# DB4100_MCU.net
KiCad netlist of a schematic drawn in Altium Designer
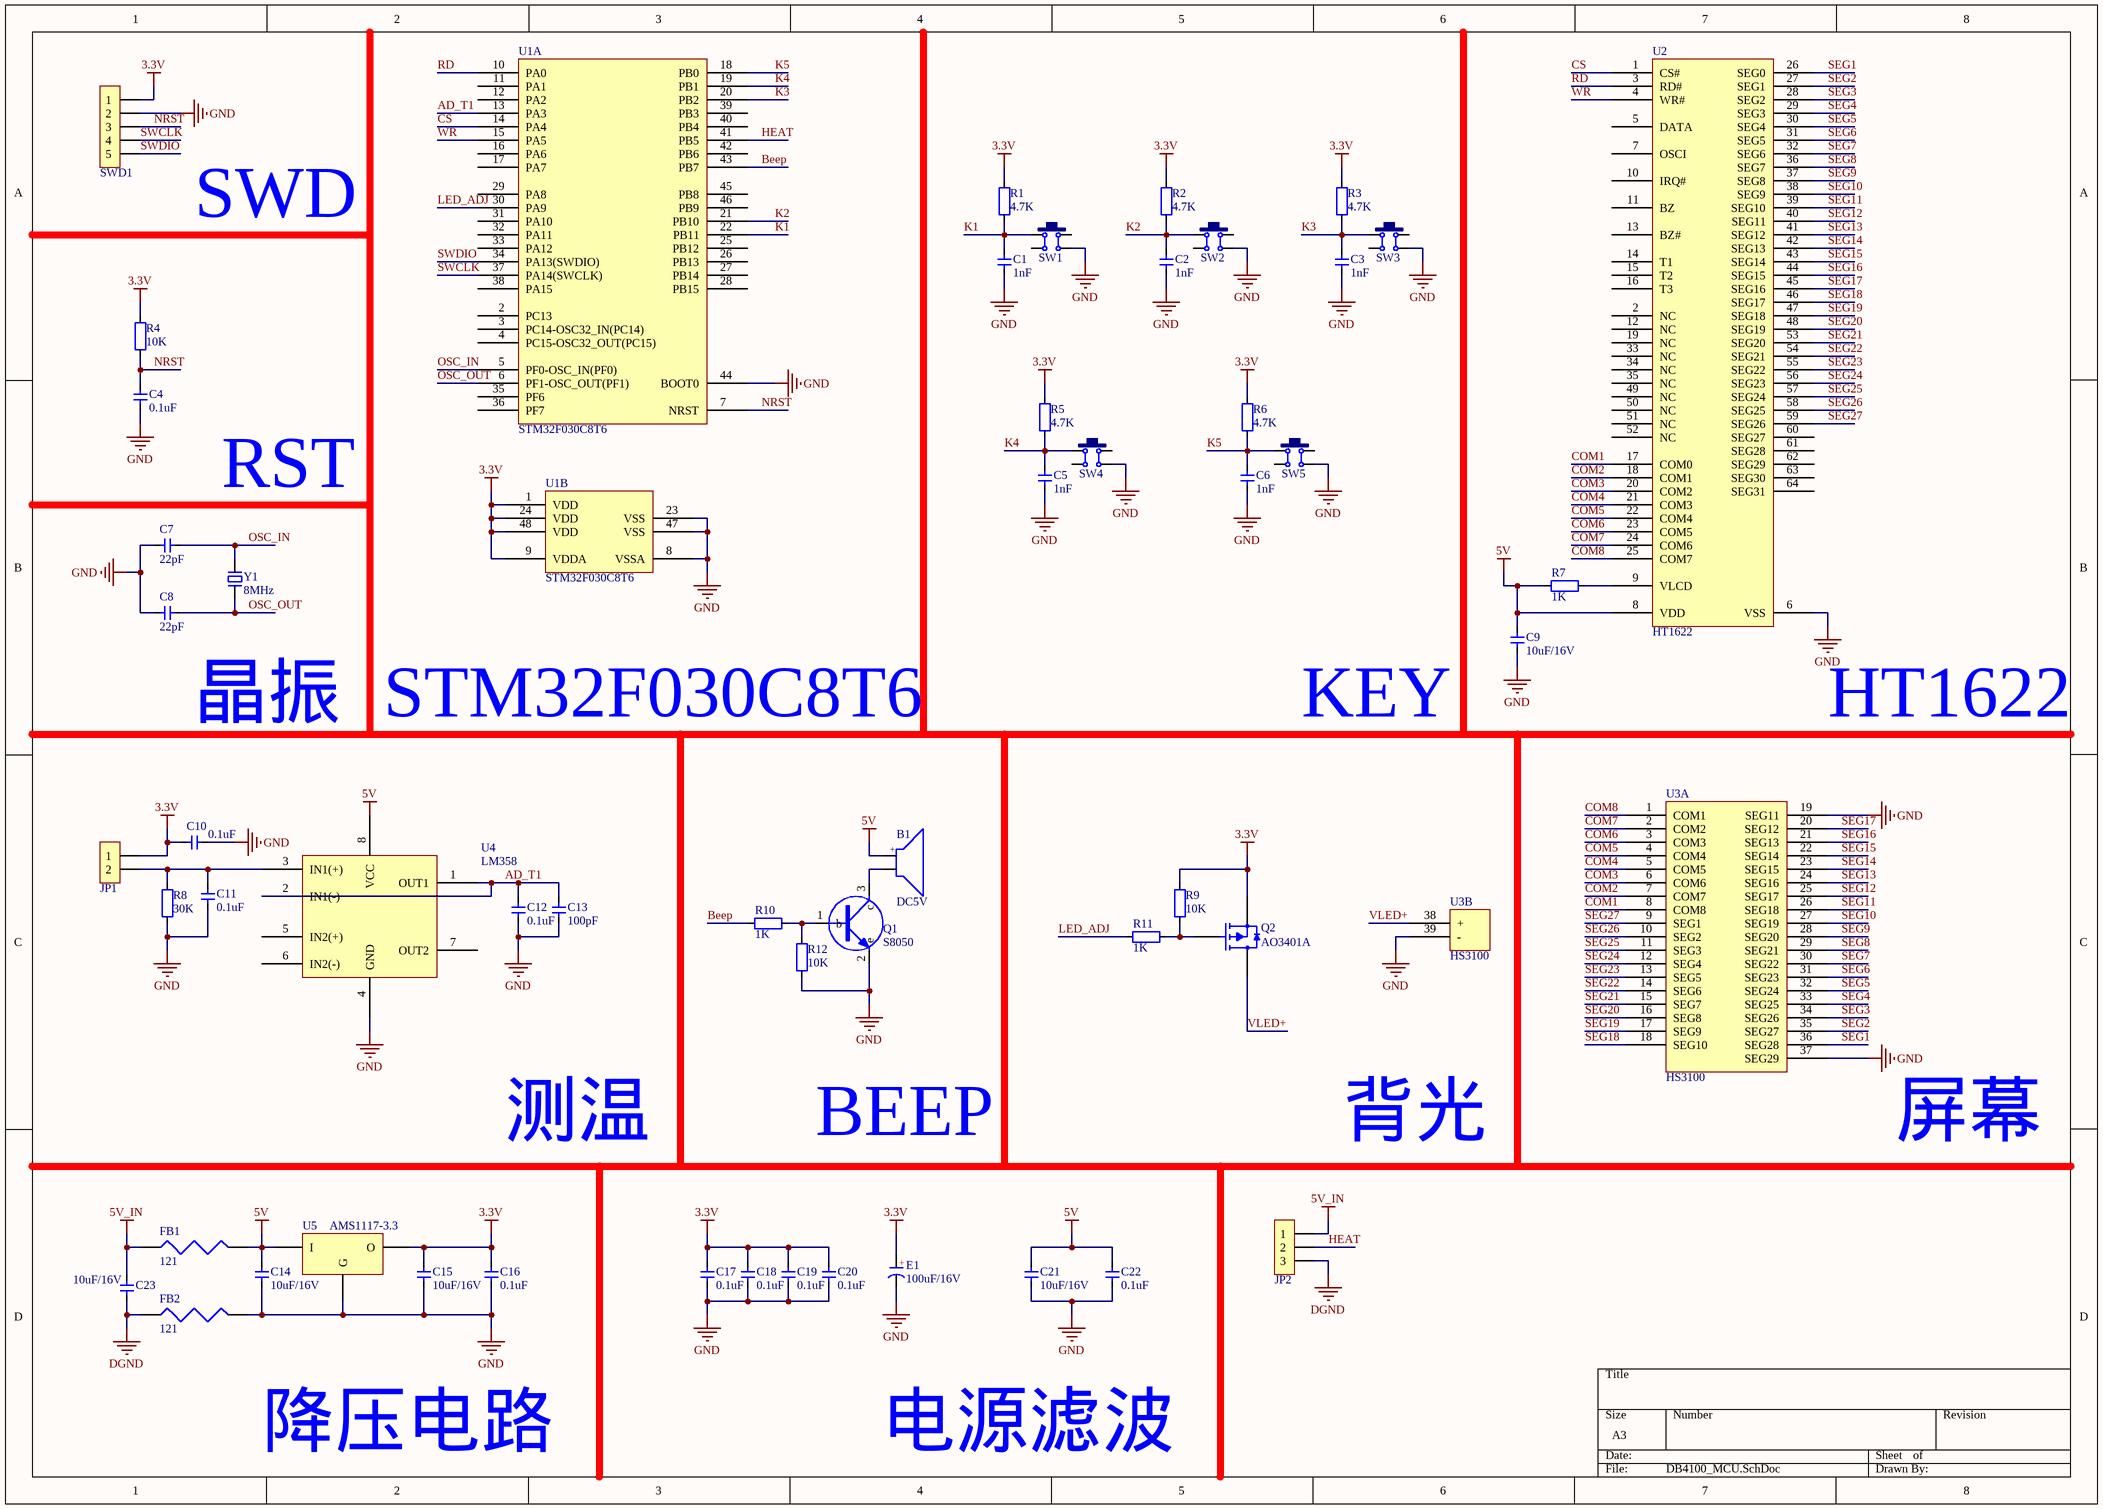
[diagram p0: DB4100_MCU.SchDoc]

(export (version "E")
  (design (tool "Eeschema 10.0.6"))
  (components
    (comp (ref "B1")
      (value "DC5V")
      (footprint "BEEP 7.6X12X7.5")
      (description "蜂鸣器")
      (fields (field (name "版权归属") "源创客"))
      (libsource (lib "模块器件") (part "BEEP"))
    )
    (comp (ref "C1")
      (value "1nF")
      (footprint "C 0603")
      (description "无极性贴片电容")
      (fields (field (name "版权归属") "源创客"))
      (libsource (lib "电容") (part "C"))
    )
    (comp (ref "C2")
      (value "1nF")
      (footprint "C 0603")
      (description "无极性贴片电容")
      (fields (field (name "版权归属") "源创客"))
      (libsource (lib "电容") (part "C"))
    )
    (comp (ref "C3")
      (value "1nF")
      (footprint "C 0603")
      (description "无极性贴片电容")
      (fields (field (name "版权归属") "源创客"))
      (libsource (lib "电容") (part "C"))
    )
    (comp (ref "C4")
      (value "0.1uF")
      (footprint "C 0603")
      (description "无极性贴片电容")
      (fields (field (name "版权归属") "源创客"))
      (libsource (lib "电容") (part "C"))
    )
    (comp (ref "C5")
      (value "1nF")
      (footprint "C 0603")
      (description "无极性贴片电容")
      (fields (field (name "版权归属") "源创客"))
      (libsource (lib "电容") (part "C"))
    )
    (comp (ref "C6")
      (value "1nF")
      (footprint "C 0603")
      (description "无极性贴片电容")
      (fields (field (name "版权归属") "源创客"))
      (libsource (lib "电容") (part "C"))
    )
    (comp (ref "C7")
      (value "22pF")
      (footprint "C 0603")
      (description "无极性贴片电容")
      (fields (field (name "版权归属") "源创客"))
      (libsource (lib "电容") (part "C"))
    )
    (comp (ref "C8")
      (value "22pF")
      (footprint "C 0603")
      (description "无极性贴片电容")
      (fields (field (name "版权归属") "源创客"))
      (libsource (lib "电容") (part "C"))
    )
    (comp (ref "C9")
      (value "10uF/16V")
      (footprint "C 0805")
      (description "无极性贴片电容")
      (fields (field (name "版权归属") "源创客"))
      (libsource (lib "电容") (part "C"))
    )
    (comp (ref "C10")
      (value "0.1uF")
      (footprint "C 0603")
      (description "无极性贴片电容")
      (fields (field (name "版权归属") "源创客"))
      (libsource (lib "电容") (part "C"))
    )
    (comp (ref "C11")
      (value "0.1uF")
      (footprint "C 0603")
      (description "无极性贴片电容")
      (fields (field (name "版权归属") "源创客"))
      (libsource (lib "电容") (part "C"))
    )
    (comp (ref "C12")
      (value "0.1uF")
      (footprint "C 0603")
      (description "无极性贴片电容")
      (fields (field (name "版权归属") "源创客"))
      (libsource (lib "电容") (part "C"))
    )
    (comp (ref "C13")
      (value "100pF")
      (footprint "C 0603")
      (description "无极性贴片电容")
      (fields (field (name "版权归属") "源创客"))
      (libsource (lib "电容") (part "C"))
    )
    (comp (ref "C14")
      (value "10uF/16V")
      (footprint "C 0805")
      (description "无极性贴片电容")
      (fields (field (name "版权归属") "源创客"))
      (libsource (lib "电容") (part "C"))
    )
    (comp (ref "C15")
      (value "10uF/16V")
      (footprint "C 0805")
      (description "无极性贴片电容")
      (fields (field (name "版权归属") "源创客"))
      (libsource (lib "电容") (part "C"))
    )
    (comp (ref "C16")
      (value "0.1uF")
      (footprint "C 0603")
      (description "无极性贴片电容")
      (fields (field (name "版权归属") "源创客"))
      (libsource (lib "电容") (part "C"))
    )
    (comp (ref "C17")
      (value "0.1uF")
      (footprint "C 0603")
      (description "无极性贴片电容")
      (fields (field (name "版权归属") "源创客"))
      (libsource (lib "电容") (part "C"))
    )
    (comp (ref "C18")
      (value "0.1uF")
      (footprint "C 0603")
      (description "无极性贴片电容")
      (fields (field (name "版权归属") "源创客"))
      (libsource (lib "电容") (part "C"))
    )
    (comp (ref "C19")
      (value "0.1uF")
      (footprint "C 0603")
      (description "无极性贴片电容")
      (fields (field (name "版权归属") "源创客"))
      (libsource (lib "电容") (part "C"))
    )
    (comp (ref "C20")
      (value "0.1uF")
      (footprint "C 0603")
      (description "无极性贴片电容")
      (fields (field (name "版权归属") "源创客"))
      (libsource (lib "电容") (part "C"))
    )
    (comp (ref "C21")
      (value "10uF/16V")
      (footprint "C 0805")
      (description "无极性贴片电容")
      (fields (field (name "版权归属") "源创客"))
      (libsource (lib "电容") (part "C"))
    )
    (comp (ref "C22")
      (value "0.1uF")
      (footprint "C 0603")
      (description "无极性贴片电容")
      (fields (field (name "版权归属") "源创客"))
      (libsource (lib "电容") (part "C"))
    )
    (comp (ref "C23")
      (value "10uF/16V")
      (footprint "C 0805")
      (description "无极性贴片电容")
      (fields (field (name "版权归属") "源创客"))
      (libsource (lib "电容") (part "C"))
    )
    (comp (ref "E1")
      (value "100uF/16V")
      (footprint "CM D(6.3*5.4)")
      (description "直插电解电容")
      (fields (field (name "版权归属") "源创客"))
      (libsource (lib "电容") (part "C-CAP"))
    )
    (comp (ref "FB1")
      (value "121")
      (footprint "L 0805")
      (description "磁珠")
      (libsource (lib "电感") (part "FB"))
    )
    (comp (ref "FB2")
      (value "121")
      (footprint "L 0805")
      (description "磁珠")
      (libsource (lib "电感") (part "FB"))
    )
    (comp (ref "JP1")
      (value "HDR-1X2")
      (footprint "XH2.54-2P")
      (description "2P接插件")
      (fields (field (name "版权归属") "源创客"))
      (libsource (lib "排针-排母") (part "Header 2"))
    )
    (comp (ref "JP2")
      (value "HDR-1X3")
      (footprint "XH2.54-3P")
      (description "3P接插件")
      (fields (field (name "版权归属") "源创客"))
      (libsource (lib "排针-排母") (part "Header 3"))
    )
    (comp (ref "Q1") (value "S8050") (footprint "SOT23-3L") (libsource (lib "三极管") (part "NPN")))
    (comp (ref "Q2")
      (value "AO3401A")
      (footprint "SOT23-3")
      (description "P-MOS")
      (libsource (lib "三极管") (part "AO3401A"))
    )
    (comp (ref "R1")
      (value "4.7K")
      (footprint "R 0603")
      (description "贴片电阻")
      (fields (field (name "版权归属") "源创客"))
      (libsource (lib "") (part "R_1"))
    )
    (comp (ref "R2")
      (value "4.7K")
      (footprint "R 0603")
      (description "贴片电阻")
      (fields (field (name "版权归属") "源创客"))
      (libsource (lib "") (part "R_1"))
    )
    (comp (ref "R3")
      (value "4.7K")
      (footprint "R 0603")
      (description "贴片电阻")
      (fields (field (name "版权归属") "源创客"))
      (libsource (lib "") (part "R_1"))
    )
    (comp (ref "R4")
      (value "10K")
      (footprint "R 0603")
      (description "贴片电阻")
      (fields (field (name "版权归属") "源创客"))
      (libsource (lib "") (part "R_1"))
    )
    (comp (ref "R5")
      (value "4.7K")
      (footprint "R 0603")
      (description "贴片电阻")
      (fields (field (name "版权归属") "源创客"))
      (libsource (lib "") (part "R_1"))
    )
    (comp (ref "R6")
      (value "4.7K")
      (footprint "R 0603")
      (description "贴片电阻")
      (fields (field (name "版权归属") "源创客"))
      (libsource (lib "") (part "R_1"))
    )
    (comp (ref "R7")
      (value "1K")
      (footprint "R 0603")
      (description "贴片电阻")
      (fields (field (name "版权归属") "源创客"))
      (libsource (lib "电阻") (part "R"))
    )
    (comp (ref "R8")
      (value "30K")
      (footprint "R 0603")
      (description "贴片电阻")
      (fields (field (name "版权归属") "源创客"))
      (libsource (lib "") (part "R_1"))
    )
    (comp (ref "R9")
      (value "10K")
      (footprint "R 0603")
      (description "贴片电阻")
      (fields (field (name "版权归属") "源创客"))
      (libsource (lib "") (part "R_1"))
    )
    (comp (ref "R10")
      (value "1K")
      (footprint "R 0603")
      (description "贴片电阻")
      (fields (field (name "版权归属") "源创客"))
      (libsource (lib "电阻") (part "R"))
    )
    (comp (ref "R11")
      (value "1K")
      (footprint "R 0603")
      (description "贴片电阻")
      (fields (field (name "版权归属") "源创客"))
      (libsource (lib "电阻") (part "R"))
    )
    (comp (ref "R12")
      (value "10K")
      (footprint "R 0603")
      (description "贴片电阻")
      (fields (field (name "版权归属") "源创客"))
      (libsource (lib "") (part "R_1"))
    )
    (comp (ref "SW1")
      (value "6x6x5")
      (footprint "TSW SMD-6*6*7")
      (description "贴片6x6轻触开关")
      (fields (field (name "版权归属") "源创客"))
      (libsource (lib "按键") (part "TSW SMD-6x6"))
    )
    (comp (ref "SW2")
      (value "6x6x5")
      (footprint "TSW SMD-6*6*7")
      (description "贴片6x6轻触开关")
      (fields (field (name "版权归属") "源创客"))
      (libsource (lib "按键") (part "TSW SMD-6x6"))
    )
    (comp (ref "SW3")
      (value "6x6x5")
      (footprint "TSW SMD-6*6*7")
      (description "贴片6x6轻触开关")
      (fields (field (name "版权归属") "源创客"))
      (libsource (lib "按键") (part "TSW SMD-6x6"))
    )
    (comp (ref "SW4")
      (value "6x6x5")
      (footprint "TSW SMD-6*6*7")
      (description "贴片6x6轻触开关")
      (fields (field (name "版权归属") "源创客"))
      (libsource (lib "按键") (part "TSW SMD-6x6"))
    )
    (comp (ref "SW5")
      (value "6x6x5")
      (footprint "TSW SMD-6*6*7")
      (description "贴片6x6轻触开关")
      (fields (field (name "版权归属") "源创客"))
      (libsource (lib "按键") (part "TSW SMD-6x6"))
    )
    (comp (ref "SWD1")
      (value "HDR-1X5")
      (footprint "XH2.54-5P")
      (description "5P接插件")
      (fields (field (name "版权归属") "源创客"))
      (libsource (lib "排针-排母") (part "Header 5"))
    )
    (comp (ref "U1")
      (value "STM32F030C8T6")
      (footprint "STM32F030C8T6")
      (libsource (lib "STM32系列单片机") (part "STM32F030C8T6"))
    )
    (comp (ref "U2")
      (value "HT1622")
      (footprint "HT1622")
      (description "LCD驱动，64引脚")
      (libsource (lib "显示芯片") (part "HT1622"))
    )
    (comp (ref "U3")
      (value "HS3100")
      (footprint "HS3100")
      (description "HS3100的屏幕")
      (libsource (lib "显示屏幕") (part "HS3100"))
    )
    (comp (ref "U4")
      (value "LM358")
      (footprint "LM358")
      (description "LM358是由两个独立的高增益运算放大器组成")
      (libsource (lib "常用芯片") (part "LM358"))
    )
    (comp (ref "U5")
      (value "AMS1117-3.3")
      (footprint "AMS1117-3.3")
      (description "转3.3V电压")
      (libsource (lib "变压器") (part "AMS1117-3.3"))
    )
    (comp (ref "Y1")
      (value "8MHz")
      (footprint "XTAL-49S SMD")
      (description "2脚晶振")
      (fields (field (name "版权归属") "源创客"))
      (libsource (lib "晶振") (part "XTAL-2"))
    )
  )
  (nets
    (net (code "1") (name "/AD_T1") (class "Default")
      (node (ref "C12") (pin "2") (pinfunction "2_2") (pintype "passive"))
      (node (ref "C13") (pin "2") (pinfunction "2_2") (pintype "passive"))
      (node (ref "U1") (pin "13") (pinfunction "PA3_13") (pintype "passive"))
      (node (ref "U4") (pin "1") (pinfunction "OUT1_1") (pintype "passive"))
      (node (ref "U4") (pin "2") (pinfunction "IN1(-)_2") (pintype "passive"))
    )
    (net (code "2") (name "/Beep") (class "Default")
      (node (ref "R10") (pin "1") (pinfunction "1_1") (pintype "passive"))
      (node (ref "U1") (pin "43") (pinfunction "PB7_43") (pintype "passive"))
    )
    (net (code "3") (name "/COM1") (class "Default")
      (node (ref "U2") (pin "17") (pinfunction "COM0_17") (pintype "passive"))
      (node (ref "U3") (pin "8") (pinfunction "COM8_8") (pintype "passive"))
    )
    (net (code "4") (name "/COM2") (class "Default")
      (node (ref "U2") (pin "18") (pinfunction "COM1_18") (pintype "passive"))
      (node (ref "U3") (pin "7") (pinfunction "COM7_7") (pintype "passive"))
    )
    (net (code "5") (name "/COM3") (class "Default")
      (node (ref "U2") (pin "20") (pinfunction "COM2_20") (pintype "passive"))
      (node (ref "U3") (pin "6") (pinfunction "COM6_6") (pintype "passive"))
    )
    (net (code "6") (name "/COM4") (class "Default")
      (node (ref "U2") (pin "21") (pinfunction "COM3_21") (pintype "passive"))
      (node (ref "U3") (pin "5") (pinfunction "COM5_5") (pintype "passive"))
    )
    (net (code "7") (name "/COM5") (class "Default")
      (node (ref "U2") (pin "22") (pinfunction "COM4_22") (pintype "passive"))
      (node (ref "U3") (pin "4") (pinfunction "COM4_4") (pintype "passive"))
    )
    (net (code "8") (name "/COM6") (class "Default")
      (node (ref "U2") (pin "23") (pinfunction "COM5_23") (pintype "passive"))
      (node (ref "U3") (pin "3") (pinfunction "COM3_3") (pintype "passive"))
    )
    (net (code "9") (name "/COM7") (class "Default")
      (node (ref "U2") (pin "24") (pinfunction "COM6_24") (pintype "passive"))
      (node (ref "U3") (pin "2") (pinfunction "COM2_2") (pintype "passive"))
    )
    (net (code "10") (name "/COM8") (class "Default")
      (node (ref "U2") (pin "25") (pinfunction "COM7_25") (pintype "passive"))
      (node (ref "U3") (pin "1") (pinfunction "COM1_1") (pintype "passive"))
    )
    (net (code "11") (name "/CS") (class "Default")
      (node (ref "U1") (pin "14") (pinfunction "PA4_14") (pintype "passive"))
      (node (ref "U2") (pin "1") (pinfunction "CS#_1") (pintype "passive"))
    )
    (net (code "12") (name "/HEAT") (class "Default")
      (node (ref "JP2") (pin "2") (pinfunction "2_2") (pintype "passive"))
      (node (ref "U1") (pin "41") (pinfunction "PB5_41") (pintype "passive"))
    )
    (net (code "13") (name "/K1") (class "Default")
      (node (ref "C1") (pin "2") (pinfunction "2_2") (pintype "passive"))
      (node (ref "R1") (pin "1") (pinfunction "1_1") (pintype "passive"))
      (node (ref "SW1") (pin "1") (pinfunction "1_1") (pintype "passive"))
      (node (ref "U1") (pin "22") (pinfunction "PB11_22") (pintype "passive"))
    )
    (net (code "14") (name "/K2") (class "Default")
      (node (ref "C2") (pin "2") (pinfunction "2_2") (pintype "passive"))
      (node (ref "R2") (pin "1") (pinfunction "1_1") (pintype "passive"))
      (node (ref "SW2") (pin "1") (pinfunction "1_1") (pintype "passive"))
      (node (ref "U1") (pin "21") (pinfunction "PB10_21") (pintype "passive"))
    )
    (net (code "15") (name "/K3") (class "Default")
      (node (ref "C3") (pin "2") (pinfunction "2_2") (pintype "passive"))
      (node (ref "R3") (pin "1") (pinfunction "1_1") (pintype "passive"))
      (node (ref "SW3") (pin "1") (pinfunction "1_1") (pintype "passive"))
      (node (ref "U1") (pin "20") (pinfunction "PB2_20") (pintype "passive"))
    )
    (net (code "16") (name "/K4") (class "Default")
      (node (ref "C5") (pin "2") (pinfunction "2_2") (pintype "passive"))
      (node (ref "R5") (pin "1") (pinfunction "1_1") (pintype "passive"))
      (node (ref "SW4") (pin "1") (pinfunction "1_1") (pintype "passive"))
      (node (ref "U1") (pin "19") (pinfunction "PB1_19") (pintype "passive"))
    )
    (net (code "17") (name "/K5") (class "Default")
      (node (ref "C6") (pin "2") (pinfunction "2_2") (pintype "passive"))
      (node (ref "R6") (pin "1") (pinfunction "1_1") (pintype "passive"))
      (node (ref "SW5") (pin "1") (pinfunction "1_1") (pintype "passive"))
      (node (ref "U1") (pin "18") (pinfunction "PB0_18") (pintype "passive"))
    )
    (net (code "18") (name "/LED_ADJ") (class "Default")
      (node (ref "R11") (pin "1") (pinfunction "1_1") (pintype "passive"))
      (node (ref "U1") (pin "30") (pinfunction "PA9_30") (pintype "passive"))
    )
    (net (code "19") (name "/NRST") (class "Default")
      (node (ref "C4") (pin "2") (pinfunction "2_2") (pintype "passive"))
      (node (ref "R4") (pin "1") (pinfunction "1_1") (pintype "passive"))
      (node (ref "SWD1") (pin "3") (pinfunction "3_3") (pintype "passive"))
      (node (ref "U1") (pin "7") (pinfunction "NRST_7") (pintype "passive"))
    )
    (net (code "20") (name "/OSC_IN") (class "Default")
      (node (ref "C7") (pin "2") (pinfunction "2_2") (pintype "passive"))
      (node (ref "U1") (pin "5") (pinfunction "PF0-OSC_IN(PF0)_5") (pintype "passive"))
      (node (ref "Y1") (pin "2") (pinfunction "2_2") (pintype "passive"))
    )
    (net (code "21") (name "/OSC_OUT") (class "Default")
      (node (ref "C8") (pin "2") (pinfunction "2_2") (pintype "passive"))
      (node (ref "U1") (pin "6") (pinfunction "PF1-OSC_OUT(PF1)_6") (pintype "passive"))
      (node (ref "Y1") (pin "1") (pinfunction "1_1") (pintype "passive"))
    )
    (net (code "22") (name "/RD") (class "Default")
      (node (ref "U1") (pin "10") (pinfunction "PA0_10") (pintype "passive"))
      (node (ref "U2") (pin "3") (pinfunction "RD#_3") (pintype "passive"))
    )
    (net (code "23") (name "/SEG1") (class "Default")
      (node (ref "U2") (pin "26") (pinfunction "SEG0_26") (pintype "passive"))
      (node (ref "U3") (pin "36") (pinfunction "SEG28_36") (pintype "passive"))
    )
    (net (code "24") (name "/SEG2") (class "Default")
      (node (ref "U2") (pin "27") (pinfunction "SEG1_27") (pintype "passive"))
      (node (ref "U3") (pin "35") (pinfunction "SEG27_35") (pintype "passive"))
    )
    (net (code "25") (name "/SEG3") (class "Default")
      (node (ref "U2") (pin "28") (pinfunction "SEG2_28") (pintype "passive"))
      (node (ref "U3") (pin "34") (pinfunction "SEG26_34") (pintype "passive"))
    )
    (net (code "26") (name "/SEG4") (class "Default")
      (node (ref "U2") (pin "29") (pinfunction "SEG3_29") (pintype "passive"))
      (node (ref "U3") (pin "33") (pinfunction "SEG25_33") (pintype "passive"))
    )
    (net (code "27") (name "/SEG5") (class "Default")
      (node (ref "U2") (pin "30") (pinfunction "SEG4_30") (pintype "passive"))
      (node (ref "U3") (pin "32") (pinfunction "SEG24_32") (pintype "passive"))
    )
    (net (code "28") (name "/SEG6") (class "Default")
      (node (ref "U2") (pin "31") (pinfunction "SEG5_31") (pintype "passive"))
      (node (ref "U3") (pin "31") (pinfunction "SEG23_31") (pintype "passive"))
    )
    (net (code "29") (name "/SEG7") (class "Default")
      (node (ref "U2") (pin "32") (pinfunction "SEG6_32") (pintype "passive"))
      (node (ref "U3") (pin "30") (pinfunction "SEG22_30") (pintype "passive"))
    )
    (net (code "30") (name "/SEG8") (class "Default")
      (node (ref "U2") (pin "36") (pinfunction "SEG7_36") (pintype "passive"))
      (node (ref "U3") (pin "29") (pinfunction "SEG21_29") (pintype "passive"))
    )
    (net (code "31") (name "/SEG9") (class "Default")
      (node (ref "U2") (pin "37") (pinfunction "SEG8_37") (pintype "passive"))
      (node (ref "U3") (pin "28") (pinfunction "SEG20_28") (pintype "passive"))
    )
    (net (code "32") (name "/SEG10") (class "Default")
      (node (ref "U2") (pin "38") (pinfunction "SEG9_38") (pintype "passive"))
      (node (ref "U3") (pin "27") (pinfunction "SEG19_27") (pintype "passive"))
    )
    (net (code "33") (name "/SEG11") (class "Default")
      (node (ref "U2") (pin "39") (pinfunction "SEG10_39") (pintype "passive"))
      (node (ref "U3") (pin "26") (pinfunction "SEG18_26") (pintype "passive"))
    )
    (net (code "34") (name "/SEG12") (class "Default")
      (node (ref "U2") (pin "40") (pinfunction "SEG11_40") (pintype "passive"))
      (node (ref "U3") (pin "25") (pinfunction "SEG17_25") (pintype "passive"))
    )
    (net (code "35") (name "/SEG13") (class "Default")
      (node (ref "U2") (pin "41") (pinfunction "SEG12_41") (pintype "passive"))
      (node (ref "U3") (pin "24") (pinfunction "SEG16_24") (pintype "passive"))
    )
    (net (code "36") (name "/SEG14") (class "Default")
      (node (ref "U2") (pin "42") (pinfunction "SEG13_42") (pintype "passive"))
      (node (ref "U3") (pin "23") (pinfunction "SEG15_23") (pintype "passive"))
    )
    (net (code "37") (name "/SEG15") (class "Default")
      (node (ref "U2") (pin "43") (pinfunction "SEG14_43") (pintype "passive"))
      (node (ref "U3") (pin "22") (pinfunction "SEG14_22") (pintype "passive"))
    )
    (net (code "38") (name "/SEG16") (class "Default")
      (node (ref "U2") (pin "44") (pinfunction "SEG15_44") (pintype "passive"))
      (node (ref "U3") (pin "21") (pinfunction "SEG13_21") (pintype "passive"))
    )
    (net (code "39") (name "/SEG17") (class "Default")
      (node (ref "U2") (pin "45") (pinfunction "SEG16_45") (pintype "passive"))
      (node (ref "U3") (pin "20") (pinfunction "SEG12_20") (pintype "passive"))
    )
    (net (code "40") (name "/SEG18") (class "Default")
      (node (ref "U2") (pin "46") (pinfunction "SEG17_46") (pintype "passive"))
      (node (ref "U3") (pin "18") (pinfunction "SEG10_18") (pintype "passive"))
    )
    (net (code "41") (name "/SEG19") (class "Default")
      (node (ref "U2") (pin "47") (pinfunction "SEG18_47") (pintype "passive"))
      (node (ref "U3") (pin "17") (pinfunction "SEG9_17") (pintype "passive"))
    )
    (net (code "42") (name "/SEG20") (class "Default")
      (node (ref "U2") (pin "48") (pinfunction "SEG19_48") (pintype "passive"))
      (node (ref "U3") (pin "16") (pinfunction "SEG8_16") (pintype "passive"))
    )
    (net (code "43") (name "/SEG21") (class "Default")
      (node (ref "U2") (pin "53") (pinfunction "SEG20_53") (pintype "passive"))
      (node (ref "U3") (pin "15") (pinfunction "SEG7_15") (pintype "passive"))
    )
    (net (code "44") (name "/SEG22") (class "Default")
      (node (ref "U2") (pin "54") (pinfunction "SEG21_54") (pintype "passive"))
      (node (ref "U3") (pin "14") (pinfunction "SEG6_14") (pintype "passive"))
    )
    (net (code "45") (name "/SEG23") (class "Default")
      (node (ref "U2") (pin "55") (pinfunction "SEG22_55") (pintype "passive"))
      (node (ref "U3") (pin "13") (pinfunction "SEG5_13") (pintype "passive"))
    )
    (net (code "46") (name "/SEG24") (class "Default")
      (node (ref "U2") (pin "56") (pinfunction "SEG23_56") (pintype "passive"))
      (node (ref "U3") (pin "12") (pinfunction "SEG4_12") (pintype "passive"))
    )
    (net (code "47") (name "/SEG25") (class "Default")
      (node (ref "U2") (pin "57") (pinfunction "SEG24_57") (pintype "passive"))
      (node (ref "U3") (pin "11") (pinfunction "SEG3_11") (pintype "passive"))
    )
    (net (code "48") (name "/SEG26") (class "Default")
      (node (ref "U2") (pin "58") (pinfunction "SEG25_58") (pintype "passive"))
      (node (ref "U3") (pin "10") (pinfunction "SEG2_10") (pintype "passive"))
    )
    (net (code "49") (name "/SEG27") (class "Default")
      (node (ref "U2") (pin "59") (pinfunction "SEG26_59") (pintype "passive"))
      (node (ref "U3") (pin "9") (pinfunction "SEG1_9") (pintype "passive"))
    )
    (net (code "50") (name "/SWCLK") (class "Default")
      (node (ref "SWD1") (pin "4") (pinfunction "4_4") (pintype "passive"))
      (node (ref "U1") (pin "37") (pinfunction "PA14(SWCLK)_37") (pintype "passive"))
    )
    (net (code "51") (name "/SWDIO") (class "Default")
      (node (ref "SWD1") (pin "5") (pinfunction "5_5") (pintype "passive"))
      (node (ref "U1") (pin "34") (pinfunction "PA13(SWDIO)_34") (pintype "passive"))
    )
    (net (code "52") (name "/VLED+") (class "Default")
      (node (ref "Q2") (pin "3") (pinfunction "D_3") (pintype "passive"))
      (node (ref "U3") (pin "38") (pinfunction "+_38") (pintype "passive"))
    )
    (net (code "53") (name "/WR") (class "Default")
      (node (ref "U1") (pin "15") (pinfunction "PA5_15") (pintype "passive"))
      (node (ref "U2") (pin "4") (pinfunction "WR#_4") (pintype "passive"))
    )
    (net (code "54") (name "3.3V") (class "Default")
      (node (ref "C10") (pin "1") (pinfunction "1_1") (pintype "passive"))
      (node (ref "C15") (pin "2") (pinfunction "2_2") (pintype "passive"))
      (node (ref "C16") (pin "2") (pinfunction "2_2") (pintype "passive"))
      (node (ref "C17") (pin "2") (pinfunction "2_2") (pintype "passive"))
      (node (ref "C18") (pin "2") (pinfunction "2_2") (pintype "passive"))
      (node (ref "C19") (pin "2") (pinfunction "2_2") (pintype "passive"))
      (node (ref "C20") (pin "2") (pinfunction "2_2") (pintype "passive"))
      (node (ref "E1") (pin "1") (pinfunction "A_1") (pintype "passive"))
      (node (ref "JP1") (pin "1") (pinfunction "1_1") (pintype "passive"))
      (node (ref "Q2") (pin "2") (pinfunction "S_2") (pintype "passive"))
      (node (ref "R1") (pin "2") (pinfunction "2_2") (pintype "passive"))
      (node (ref "R2") (pin "2") (pinfunction "2_2") (pintype "passive"))
      (node (ref "R3") (pin "2") (pinfunction "2_2") (pintype "passive"))
      (node (ref "R4") (pin "2") (pinfunction "2_2") (pintype "passive"))
      (node (ref "R5") (pin "2") (pinfunction "2_2") (pintype "passive"))
      (node (ref "R6") (pin "2") (pinfunction "2_2") (pintype "passive"))
      (node (ref "R9") (pin "2") (pinfunction "2_2") (pintype "passive"))
      (node (ref "SWD1") (pin "1") (pinfunction "1_1") (pintype "passive"))
      (node (ref "U1") (pin "1") (pinfunction "VDD_1") (pintype "passive"))
      (node (ref "U1") (pin "24") (pinfunction "VDD_24") (pintype "passive"))
      (node (ref "U1") (pin "48") (pinfunction "VDD_48") (pintype "passive"))
      (node (ref "U1") (pin "9") (pinfunction "VDDA_9") (pintype "passive"))
      (node (ref "U5") (pin "2") (pinfunction "O_2") (pintype "passive"))
    )
    (net (code "55") (name "5V") (class "Default")
      (node (ref "B1") (pin "1") (pinfunction "1_1") (pintype "passive"))
      (node (ref "C14") (pin "2") (pinfunction "2_2") (pintype "passive"))
      (node (ref "C21") (pin "2") (pinfunction "2_2") (pintype "passive"))
      (node (ref "C22") (pin "2") (pinfunction "2_2") (pintype "passive"))
      (node (ref "C9") (pin "2") (pinfunction "2_2") (pintype "passive"))
      (node (ref "FB1") (pin "2") (pinfunction "2_2") (pintype "passive"))
      (node (ref "R7") (pin "1") (pinfunction "1_1") (pintype "passive"))
      (node (ref "U2") (pin "8") (pinfunction "VDD_8") (pintype "passive"))
      (node (ref "U4") (pin "8") (pinfunction "VCC_8") (pintype "passive"))
      (node (ref "U5") (pin "3") (pinfunction "I_3") (pintype "passive"))
    )
    (net (code "56") (name "5V_IN") (class "Default")
      (node (ref "C23") (pin "2") (pinfunction "2_2") (pintype "passive"))
      (node (ref "FB1") (pin "1") (pinfunction "1_1") (pintype "passive"))
      (node (ref "JP2") (pin "1") (pinfunction "1_1") (pintype "passive"))
    )
    (net (code "57") (name "DGND") (class "Default")
      (node (ref "C23") (pin "1") (pinfunction "1_1") (pintype "passive"))
      (node (ref "FB2") (pin "1") (pinfunction "1_1") (pintype "passive"))
      (node (ref "JP2") (pin "3") (pinfunction "3_3") (pintype "passive"))
    )
    (net (code "58") (name "GND") (class "Default")
      (node (ref "C1") (pin "1") (pinfunction "1_1") (pintype "passive"))
      (node (ref "C10") (pin "2") (pinfunction "2_2") (pintype "passive"))
      (node (ref "C11") (pin "1") (pinfunction "1_1") (pintype "passive"))
      (node (ref "C12") (pin "1") (pinfunction "1_1") (pintype "passive"))
      (node (ref "C13") (pin "1") (pinfunction "1_1") (pintype "passive"))
      (node (ref "C14") (pin "1") (pinfunction "1_1") (pintype "passive"))
      (node (ref "C15") (pin "1") (pinfunction "1_1") (pintype "passive"))
      (node (ref "C16") (pin "1") (pinfunction "1_1") (pintype "passive"))
      (node (ref "C17") (pin "1") (pinfunction "1_1") (pintype "passive"))
      (node (ref "C18") (pin "1") (pinfunction "1_1") (pintype "passive"))
      (node (ref "C19") (pin "1") (pinfunction "1_1") (pintype "passive"))
      (node (ref "C2") (pin "1") (pinfunction "1_1") (pintype "passive"))
      (node (ref "C20") (pin "1") (pinfunction "1_1") (pintype "passive"))
      (node (ref "C21") (pin "1") (pinfunction "1_1") (pintype "passive"))
      (node (ref "C22") (pin "1") (pinfunction "1_1") (pintype "passive"))
      (node (ref "C3") (pin "1") (pinfunction "1_1") (pintype "passive"))
      (node (ref "C4") (pin "1") (pinfunction "1_1") (pintype "passive"))
      (node (ref "C5") (pin "1") (pinfunction "1_1") (pintype "passive"))
      (node (ref "C6") (pin "1") (pinfunction "1_1") (pintype "passive"))
      (node (ref "C7") (pin "1") (pinfunction "1_1") (pintype "passive"))
      (node (ref "C8") (pin "1") (pinfunction "1_1") (pintype "passive"))
      (node (ref "C9") (pin "1") (pinfunction "1_1") (pintype "passive"))
      (node (ref "E1") (pin "2") (pinfunction "K_2") (pintype "passive"))
      (node (ref "FB2") (pin "2") (pinfunction "2_2") (pintype "passive"))
      (node (ref "Q1") (pin "2") (pinfunction "e_2") (pintype "passive"))
      (node (ref "R12") (pin "1") (pinfunction "1_1") (pintype "passive"))
      (node (ref "R8") (pin "1") (pinfunction "1_1") (pintype "passive"))
      (node (ref "SW1") (pin "3") (pinfunction "3_3") (pintype "passive"))
      (node (ref "SW2") (pin "3") (pinfunction "3_3") (pintype "passive"))
      (node (ref "SW3") (pin "3") (pinfunction "3_3") (pintype "passive"))
      (node (ref "SW4") (pin "3") (pinfunction "3_3") (pintype "passive"))
      (node (ref "SW5") (pin "3") (pinfunction "3_3") (pintype "passive"))
      (node (ref "SWD1") (pin "2") (pinfunction "2_2") (pintype "passive"))
      (node (ref "U1") (pin "23") (pinfunction "VSS_23") (pintype "passive"))
      (node (ref "U1") (pin "44") (pinfunction "BOOT0_44") (pintype "passive"))
      (node (ref "U1") (pin "47") (pinfunction "VSS_47") (pintype "passive"))
      (node (ref "U1") (pin "8") (pinfunction "VSSA_8") (pintype "passive"))
      (node (ref "U2") (pin "6") (pinfunction "VSS_6") (pintype "passive"))
      (node (ref "U3") (pin "19") (pinfunction "SEG11_19") (pintype "passive"))
      (node (ref "U3") (pin "37") (pinfunction "SEG29_37") (pintype "passive"))
      (node (ref "U3") (pin "39") (pinfunction "-_39") (pintype "passive"))
      (node (ref "U4") (pin "4") (pinfunction "GND_4") (pintype "passive"))
      (node (ref "U5") (pin "1") (pinfunction "G_1") (pintype "passive"))
    )
    (net (code "59") (name "Net-(Q1-b)") (class "Default")
      (node (ref "Q1") (pin "1") (pinfunction "b_1") (pintype "passive"))
      (node (ref "R10") (pin "2") (pinfunction "2_2") (pintype "passive"))
      (node (ref "R12") (pin "2") (pinfunction "2_2") (pintype "passive"))
    )
    (net (code "60") (name "Net-(Q1-c)") (class "Default")
      (node (ref "B1") (pin "2") (pinfunction "2_2") (pintype "passive"))
      (node (ref "Q1") (pin "3") (pinfunction "c_3") (pintype "passive"))
    )
    (net (code "61") (name "Net-(Q2-G)") (class "Default")
      (node (ref "Q2") (pin "1") (pinfunction "G_1") (pintype "passive"))
      (node (ref "R11") (pin "2") (pinfunction "2_2") (pintype "passive"))
      (node (ref "R9") (pin "1") (pinfunction "1_1") (pintype "passive"))
    )
    (net (code "62") (name "Net-(U2-VLCD)") (class "Default")
      (node (ref "R7") (pin "2") (pinfunction "2_2") (pintype "passive"))
      (node (ref "U2") (pin "9") (pinfunction "VLCD_9") (pintype "passive"))
    )
    (net (code "63") (name "Net-(U4-IN1(+))") (class "Default")
      (node (ref "C11") (pin "2") (pinfunction "2_2") (pintype "passive"))
      (node (ref "JP1") (pin "2") (pinfunction "2_2") (pintype "passive"))
      (node (ref "R8") (pin "2") (pinfunction "2_2") (pintype "passive"))
      (node (ref "U4") (pin "3") (pinfunction "IN1(+)_3") (pintype "passive"))
    )
    (net (code "64") (name "unconnected-(SW1-Pad2)") (class "Default")
      (node (ref "SW1") (pin "2") (pinfunction "2_2") (pintype "passive"))
    )
    (net (code "65") (name "unconnected-(SW1-Pad4)") (class "Default")
      (node (ref "SW1") (pin "4") (pinfunction "4_4") (pintype "passive"))
    )
    (net (code "66") (name "unconnected-(SW2-Pad2)") (class "Default")
      (node (ref "SW2") (pin "2") (pinfunction "2_2") (pintype "passive"))
    )
    (net (code "67") (name "unconnected-(SW2-Pad4)") (class "Default")
      (node (ref "SW2") (pin "4") (pinfunction "4_4") (pintype "passive"))
    )
    (net (code "68") (name "unconnected-(SW3-Pad2)") (class "Default")
      (node (ref "SW3") (pin "2") (pinfunction "2_2") (pintype "passive"))
    )
    (net (code "69") (name "unconnected-(SW3-Pad4)") (class "Default")
      (node (ref "SW3") (pin "4") (pinfunction "4_4") (pintype "passive"))
    )
    (net (code "70") (name "unconnected-(SW4-Pad2)") (class "Default")
      (node (ref "SW4") (pin "2") (pinfunction "2_2") (pintype "passive"))
    )
    (net (code "71") (name "unconnected-(SW4-Pad4)") (class "Default")
      (node (ref "SW4") (pin "4") (pinfunction "4_4") (pintype "passive"))
    )
    (net (code "72") (name "unconnected-(SW5-Pad2)") (class "Default")
      (node (ref "SW5") (pin "2") (pinfunction "2_2") (pintype "passive"))
    )
    (net (code "73") (name "unconnected-(SW5-Pad4)") (class "Default")
      (node (ref "SW5") (pin "4") (pinfunction "4_4") (pintype "passive"))
    )
    (net (code "74") (name "unconnected-(U1A-PA1-Pad11)") (class "Default")
      (node (ref "U1") (pin "11") (pinfunction "PA1_11") (pintype "passive"))
    )
    (net (code "75") (name "unconnected-(U1A-PA2-Pad12)") (class "Default")
      (node (ref "U1") (pin "12") (pinfunction "PA2_12") (pintype "passive"))
    )
    (net (code "76") (name "unconnected-(U1A-PA6-Pad16)") (class "Default")
      (node (ref "U1") (pin "16") (pinfunction "PA6_16") (pintype "passive"))
    )
    (net (code "77") (name "unconnected-(U1A-PA7-Pad17)") (class "Default")
      (node (ref "U1") (pin "17") (pinfunction "PA7_17") (pintype "passive"))
    )
    (net (code "78") (name "unconnected-(U1A-PA8-Pad29)") (class "Default")
      (node (ref "U1") (pin "29") (pinfunction "PA8_29") (pintype "passive"))
    )
    (net (code "79") (name "unconnected-(U1A-PA10-Pad31)") (class "Default")
      (node (ref "U1") (pin "31") (pinfunction "PA10_31") (pintype "passive"))
    )
    (net (code "80") (name "unconnected-(U1A-PA11-Pad32)") (class "Default")
      (node (ref "U1") (pin "32") (pinfunction "PA11_32") (pintype "passive"))
    )
    (net (code "81") (name "unconnected-(U1A-PA12-Pad33)") (class "Default")
      (node (ref "U1") (pin "33") (pinfunction "PA12_33") (pintype "passive"))
    )
    (net (code "82") (name "unconnected-(U1A-PA15-Pad38)") (class "Default")
      (node (ref "U1") (pin "38") (pinfunction "PA15_38") (pintype "passive"))
    )
    (net (code "83") (name "unconnected-(U1A-PB3-Pad39)") (class "Default")
      (node (ref "U1") (pin "39") (pinfunction "PB3_39") (pintype "passive"))
    )
    (net (code "84") (name "unconnected-(U1A-PB4-Pad40)") (class "Default")
      (node (ref "U1") (pin "40") (pinfunction "PB4_40") (pintype "passive"))
    )
    (net (code "85") (name "unconnected-(U1A-PB6-Pad42)") (class "Default")
      (node (ref "U1") (pin "42") (pinfunction "PB6_42") (pintype "passive"))
    )
    (net (code "86") (name "unconnected-(U1A-PB8-Pad45)") (class "Default")
      (node (ref "U1") (pin "45") (pinfunction "PB8_45") (pintype "passive"))
    )
    (net (code "87") (name "unconnected-(U1A-PB9-Pad46)") (class "Default")
      (node (ref "U1") (pin "46") (pinfunction "PB9_46") (pintype "passive"))
    )
    (net (code "88") (name "unconnected-(U1A-PB12-Pad25)") (class "Default")
      (node (ref "U1") (pin "25") (pinfunction "PB12_25") (pintype "passive"))
    )
    (net (code "89") (name "unconnected-(U1A-PB13-Pad26)") (class "Default")
      (node (ref "U1") (pin "26") (pinfunction "PB13_26") (pintype "passive"))
    )
    (net (code "90") (name "unconnected-(U1A-PB14-Pad27)") (class "Default")
      (node (ref "U1") (pin "27") (pinfunction "PB14_27") (pintype "passive"))
    )
    (net (code "91") (name "unconnected-(U1A-PB15-Pad28)") (class "Default")
      (node (ref "U1") (pin "28") (pinfunction "PB15_28") (pintype "passive"))
    )
    (net (code "92") (name "unconnected-(U1A-PC13-Pad2)") (class "Default")
      (node (ref "U1") (pin "2") (pinfunction "PC13_2") (pintype "passive"))
    )
    (net (code "93") (name "unconnected-(U1A-PC14-OSC32_IN(PC14)-Pad3)") (class "Default")
      (node (ref "U1") (pin "3") (pinfunction "PC14-OSC32_IN(PC14)_3") (pintype "passive"))
    )
    (net (code "94") (name "unconnected-(U1A-PC15-OSC32_OUT(PC15)-Pad4)") (class "Default")
      (node (ref "U1") (pin "4") (pinfunction "PC15-OSC32_OUT(PC15)_4") (pintype "passive"))
    )
    (net (code "95") (name "unconnected-(U1A-PF6-Pad35)") (class "Default")
      (node (ref "U1") (pin "35") (pinfunction "PF6_35") (pintype "passive"))
    )
    (net (code "96") (name "unconnected-(U1A-PF7-Pad36)") (class "Default")
      (node (ref "U1") (pin "36") (pinfunction "PF7_36") (pintype "passive"))
    )
    (net (code "97") (name "unconnected-(U2-BZ#-Pad13)") (class "Default")
      (node (ref "U2") (pin "13") (pinfunction "BZ#_13") (pintype "passive"))
    )
    (net (code "98") (name "unconnected-(U2-BZ-Pad11)") (class "Default")
      (node (ref "U2") (pin "11") (pinfunction "BZ_11") (pintype "passive"))
    )
    (net (code "99") (name "unconnected-(U2-DATA-Pad5)") (class "Default")
      (node (ref "U2") (pin "5") (pinfunction "DATA_5") (pintype "passive"))
    )
    (net (code "100") (name "unconnected-(U2-IRQ#-Pad10)") (class "Default")
      (node (ref "U2") (pin "10") (pinfunction "IRQ#_10") (pintype "passive"))
    )
    (net (code "101") (name "unconnected-(U2-NC-Pad2)") (class "Default")
      (node (ref "U2") (pin "2") (pinfunction "NC_2") (pintype "passive"))
    )
    (net (code "102") (name "unconnected-(U2-NC-Pad12)") (class "Default")
      (node (ref "U2") (pin "12") (pinfunction "NC_12") (pintype "passive"))
    )
    (net (code "103") (name "unconnected-(U2-NC-Pad19)") (class "Default")
      (node (ref "U2") (pin "19") (pinfunction "NC_19") (pintype "passive"))
    )
    (net (code "104") (name "unconnected-(U2-NC-Pad33)") (class "Default")
      (node (ref "U2") (pin "33") (pinfunction "NC_33") (pintype "passive"))
    )
    (net (code "105") (name "unconnected-(U2-NC-Pad34)") (class "Default")
      (node (ref "U2") (pin "34") (pinfunction "NC_34") (pintype "passive"))
    )
    (net (code "106") (name "unconnected-(U2-NC-Pad35)") (class "Default")
      (node (ref "U2") (pin "35") (pinfunction "NC_35") (pintype "passive"))
    )
    (net (code "107") (name "unconnected-(U2-NC-Pad49)") (class "Default")
      (node (ref "U2") (pin "49") (pinfunction "NC_49") (pintype "passive"))
    )
    (net (code "108") (name "unconnected-(U2-NC-Pad50)") (class "Default")
      (node (ref "U2") (pin "50") (pinfunction "NC_50") (pintype "passive"))
    )
    (net (code "109") (name "unconnected-(U2-NC-Pad51)") (class "Default")
      (node (ref "U2") (pin "51") (pinfunction "NC_51") (pintype "passive"))
    )
    (net (code "110") (name "unconnected-(U2-NC-Pad52)") (class "Default")
      (node (ref "U2") (pin "52") (pinfunction "NC_52") (pintype "passive"))
    )
    (net (code "111") (name "unconnected-(U2-OSCI-Pad7)") (class "Default")
      (node (ref "U2") (pin "7") (pinfunction "OSCI_7") (pintype "passive"))
    )
    (net (code "112") (name "unconnected-(U2-SEG27-Pad60)") (class "Default")
      (node (ref "U2") (pin "60") (pinfunction "SEG27_60") (pintype "passive"))
    )
    (net (code "113") (name "unconnected-(U2-SEG28-Pad61)") (class "Default")
      (node (ref "U2") (pin "61") (pinfunction "SEG28_61") (pintype "passive"))
    )
    (net (code "114") (name "unconnected-(U2-SEG29-Pad62)") (class "Default")
      (node (ref "U2") (pin "62") (pinfunction "SEG29_62") (pintype "passive"))
    )
    (net (code "115") (name "unconnected-(U2-SEG30-Pad63)") (class "Default")
      (node (ref "U2") (pin "63") (pinfunction "SEG30_63") (pintype "passive"))
    )
    (net (code "116") (name "unconnected-(U2-SEG31-Pad64)") (class "Default")
      (node (ref "U2") (pin "64") (pinfunction "SEG31_64") (pintype "passive"))
    )
    (net (code "117") (name "unconnected-(U2-T1-Pad14)") (class "Default")
      (node (ref "U2") (pin "14") (pinfunction "T1_14") (pintype "passive"))
    )
    (net (code "118") (name "unconnected-(U2-T2-Pad15)") (class "Default")
      (node (ref "U2") (pin "15") (pinfunction "T2_15") (pintype "passive"))
    )
    (net (code "119") (name "unconnected-(U2-T3-Pad16)") (class "Default")
      (node (ref "U2") (pin "16") (pinfunction "T3_16") (pintype "passive"))
    )
    (net (code "120") (name "unconnected-(U4-IN2(+)-Pad5)") (class "Default")
      (node (ref "U4") (pin "5") (pinfunction "IN2(+)_5") (pintype "passive"))
    )
    (net (code "121") (name "unconnected-(U4-IN2(-)-Pad6)") (class "Default")
      (node (ref "U4") (pin "6") (pinfunction "IN2(-)_6") (pintype "passive"))
    )
    (net (code "122") (name "unconnected-(U4-OUT2-Pad7)") (class "Default")
      (node (ref "U4") (pin "7") (pinfunction "OUT2_7") (pintype "passive"))
    )
  )
)
